# SCH_NRF_Rapid_Test_Board_2021-07-05.net
KiCad netlist of a schematic drawn in EasyEDA
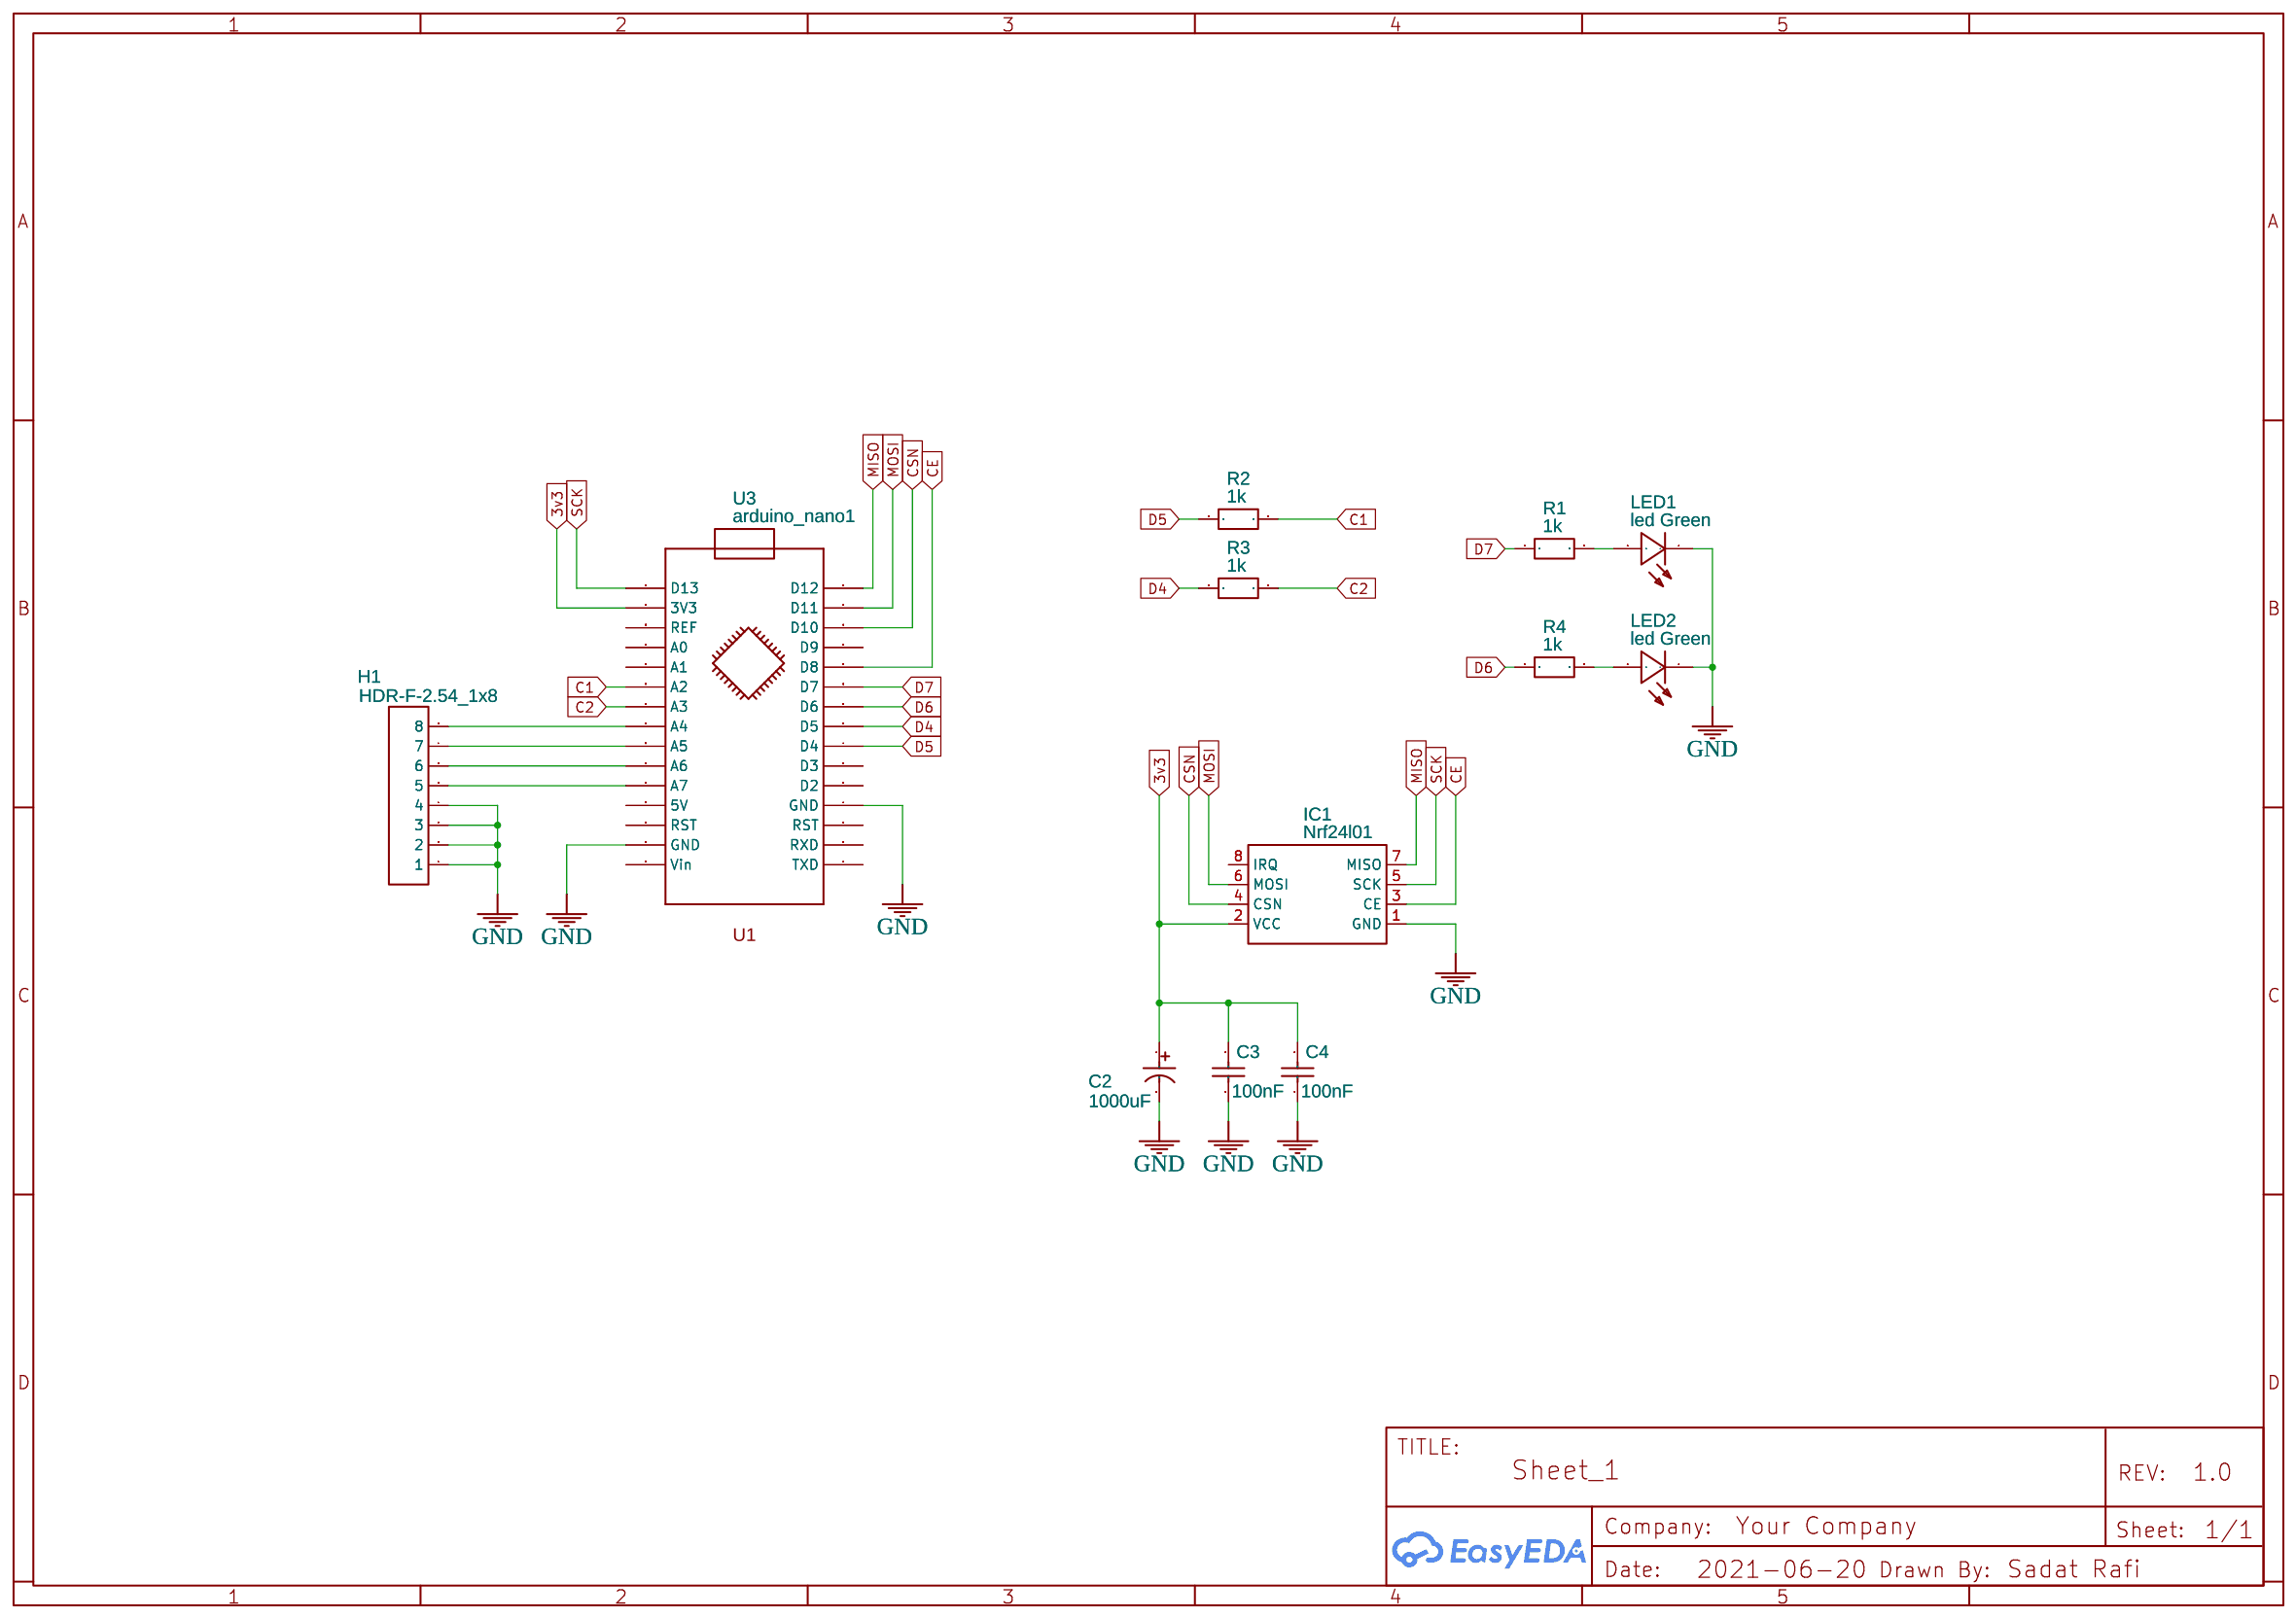
[diagram p0: schematic sheet]

(export (version "E")
  (design (tool "Eeschema 10.0.6"))
  (components
    (comp (ref "C2")
      (value "1000uF")
      (fields (field (name "BOM_Manufacturer Part") "1000uF 16V") (field (name "BOM_Supplier Part") "C43909"))
      (libsource (lib "") (part "1000uF 16V"))
    )
    (comp (ref "C3")
      (value "100nF")
      (fields
        (field (name "BOM_Manufacturer Part") "CL31B104KBCNNNC")
        (field (name "BOM_Supplier Part") "C24497")
      )
      (libsource (lib "") (part "CL31B104KBCNNNC"))
    )
    (comp (ref "C4")
      (value "100nF")
      (fields
        (field (name "BOM_Manufacturer Part") "CL31B104KBCNNNC")
        (field (name "BOM_Supplier Part") "C24497")
      )
      (libsource (lib "") (part "CL31B104KBCNNNC"))
    )
    (comp (ref "H1")
      (value "HDR-F-2.54_1x8")
      (fields (field (name "BOM_Supplier Part") "C225505"))
      (libsource (lib "") (part "HDR-F-2.54_1x8"))
    )
    (comp (ref "IC1")
      (value "Nrf24l01")
      (fields (field (name "BOM_Manufacturer Part") "NRF24L01") (field (name "BOM_Supplier Part") "01"))
      (libsource (lib "") (part "Nrf24l01"))
    )
    (comp (ref "LED1")
      (value "led Green")
      (fields (field (name "BOM_Supplier Part") "C14641"))
      (libsource (lib "") (part "led Green"))
    )
    (comp (ref "LED2")
      (value "led Green")
      (fields (field (name "BOM_Supplier Part") "C14641"))
      (libsource (lib "") (part "led Green"))
    )
    (comp (ref "R1") (value "1k") (libsource (lib "") (part "R_1206_EU")))
    (comp (ref "R2") (value "1k") (libsource (lib "") (part "R_1206_EU")))
    (comp (ref "R3") (value "1k") (libsource (lib "") (part "R_1206_EU")))
    (comp (ref "R4") (value "1k") (libsource (lib "") (part "R_1206_EU")))
    (comp (ref "U3") (value "arduino_nano1") (libsource (lib "") (part "arduino_nano1")))
  )
  (nets
    (net (code "1") (name "3v3") (class "Default")
      (node (ref "C2") (pin "1") (pinfunction "1_1") (pintype "input"))
      (node (ref "C3") (pin "2") (pinfunction "2_2") (pintype "input"))
      (node (ref "C4") (pin "2") (pinfunction "2_2") (pintype "input"))
      (node (ref "IC1") (pin "2") (pinfunction "VCC_2") (pintype "unspecified"))
      (node (ref "U3") (pin "17") (pinfunction "3V3_17") (pintype "unspecified"))
    )
    (net (code "2") (name "C1") (class "Default")
      (node (ref "R2") (pin "2") (pinfunction "2_2") (pintype "unspecified"))
      (node (ref "U3") (pin "21") (pinfunction "A2_21") (pintype "unspecified"))
    )
    (net (code "3") (name "C2") (class "Default")
      (node (ref "R3") (pin "2") (pinfunction "2_2") (pintype "unspecified"))
      (node (ref "U3") (pin "22") (pinfunction "A3_22") (pintype "unspecified"))
    )
    (net (code "4") (name "CE") (class "Default")
      (node (ref "IC1") (pin "3") (pinfunction "CE_3") (pintype "unspecified"))
      (node (ref "U3") (pin "11") (pinfunction "D8_11") (pintype "unspecified"))
    )
    (net (code "5") (name "CSN") (class "Default")
      (node (ref "IC1") (pin "4") (pinfunction "CSN_4") (pintype "unspecified"))
      (node (ref "U3") (pin "13") (pinfunction "D10_13") (pintype "unspecified"))
    )
    (net (code "6") (name "D4") (class "Default")
      (node (ref "R3") (pin "1") (pinfunction "1_1") (pintype "unspecified"))
      (node (ref "U3") (pin "8") (pinfunction "D5_8") (pintype "unspecified"))
    )
    (net (code "7") (name "D5") (class "Default")
      (node (ref "R2") (pin "1") (pinfunction "1_1") (pintype "unspecified"))
      (node (ref "U3") (pin "7") (pinfunction "D4_7") (pintype "unspecified"))
    )
    (net (code "8") (name "D6") (class "Default")
      (node (ref "R4") (pin "1") (pinfunction "1_1") (pintype "unspecified"))
      (node (ref "U3") (pin "9") (pinfunction "D6_9") (pintype "unspecified"))
    )
    (net (code "9") (name "D7") (class "Default")
      (node (ref "R1") (pin "1") (pinfunction "1_1") (pintype "unspecified"))
      (node (ref "U3") (pin "10") (pinfunction "D7_10") (pintype "unspecified"))
    )
    (net (code "10") (name "GND") (class "Default")
      (node (ref "C2") (pin "2") (pinfunction "2_2") (pintype "input"))
      (node (ref "C3") (pin "1") (pinfunction "1_1") (pintype "input"))
      (node (ref "C4") (pin "1") (pinfunction "1_1") (pintype "input"))
      (node (ref "H1") (pin "1") (pinfunction "1_1") (pintype "unspecified"))
      (node (ref "H1") (pin "2") (pinfunction "2_2") (pintype "unspecified"))
      (node (ref "H1") (pin "3") (pinfunction "3_3") (pintype "unspecified"))
      (node (ref "H1") (pin "4") (pinfunction "4_4") (pintype "unspecified"))
      (node (ref "IC1") (pin "1") (pinfunction "GND_1") (pintype "unspecified"))
      (node (ref "LED1") (pin "1") (pinfunction "-_1") (pintype "unspecified"))
      (node (ref "LED2") (pin "1") (pinfunction "-_1") (pintype "unspecified"))
      (node (ref "U3") (pin "29") (pinfunction "GND_29") (pintype "unspecified"))
      (node (ref "U3") (pin "4") (pinfunction "GND_4") (pintype "unspecified"))
    )
    (net (code "11") (name "MISO") (class "Default")
      (node (ref "IC1") (pin "7") (pinfunction "MISO_7") (pintype "unspecified"))
      (node (ref "U3") (pin "15") (pinfunction "D12_15") (pintype "unspecified"))
    )
    (net (code "12") (name "MOSI") (class "Default")
      (node (ref "IC1") (pin "6") (pinfunction "MOSI_6") (pintype "unspecified"))
      (node (ref "U3") (pin "14") (pinfunction "D11_14") (pintype "unspecified"))
    )
    (net (code "13") (name "Net-(LED1-+)") (class "Default")
      (node (ref "LED1") (pin "2") (pinfunction "+_2") (pintype "unspecified"))
      (node (ref "R1") (pin "2") (pinfunction "2_2") (pintype "unspecified"))
    )
    (net (code "14") (name "Net-(LED2-+)") (class "Default")
      (node (ref "LED2") (pin "2") (pinfunction "+_2") (pintype "unspecified"))
      (node (ref "R4") (pin "2") (pinfunction "2_2") (pintype "unspecified"))
    )
    (net (code "15") (name "Net-(U3-A4)") (class "Default")
      (node (ref "H1") (pin "8") (pinfunction "8_8") (pintype "unspecified"))
      (node (ref "U3") (pin "23") (pinfunction "A4_23") (pintype "unspecified"))
    )
    (net (code "16") (name "Net-(U3-A5)") (class "Default")
      (node (ref "H1") (pin "7") (pinfunction "7_7") (pintype "unspecified"))
      (node (ref "U3") (pin "24") (pinfunction "A5_24") (pintype "unspecified"))
    )
    (net (code "17") (name "Net-(U3-A6)") (class "Default")
      (node (ref "H1") (pin "6") (pinfunction "6_6") (pintype "unspecified"))
      (node (ref "U3") (pin "25") (pinfunction "A6_25") (pintype "unspecified"))
    )
    (net (code "18") (name "Net-(U3-A7)") (class "Default")
      (node (ref "H1") (pin "5") (pinfunction "5_5") (pintype "unspecified"))
      (node (ref "U3") (pin "26") (pinfunction "A7_26") (pintype "unspecified"))
    )
    (net (code "19") (name "SCK") (class "Default")
      (node (ref "IC1") (pin "5") (pinfunction "SCK_5") (pintype "unspecified"))
      (node (ref "U3") (pin "16") (pinfunction "D13_16") (pintype "unspecified"))
    )
    (net (code "20") (name "unconnected-(IC1-IRQ-Pad8)") (class "Default")
      (node (ref "IC1") (pin "8") (pinfunction "IRQ_8") (pintype "unspecified"))
    )
    (net (code "21") (name "unconnected-(U3-5V-Pad27)") (class "Default")
      (node (ref "U3") (pin "27") (pinfunction "5V_27") (pintype "unspecified"))
    )
    (net (code "22") (name "unconnected-(U3-A0-Pad19)") (class "Default")
      (node (ref "U3") (pin "19") (pinfunction "A0_19") (pintype "unspecified"))
    )
    (net (code "23") (name "unconnected-(U3-A1-Pad20)") (class "Default")
      (node (ref "U3") (pin "20") (pinfunction "A1_20") (pintype "unspecified"))
    )
    (net (code "24") (name "unconnected-(U3-D2-Pad5)") (class "Default")
      (node (ref "U3") (pin "5") (pinfunction "D2_5") (pintype "unspecified"))
    )
    (net (code "25") (name "unconnected-(U3-D3-Pad6)") (class "Default")
      (node (ref "U3") (pin "6") (pinfunction "D3_6") (pintype "unspecified"))
    )
    (net (code "26") (name "unconnected-(U3-D9-Pad12)") (class "Default")
      (node (ref "U3") (pin "12") (pinfunction "D9_12") (pintype "unspecified"))
    )
    (net (code "27") (name "unconnected-(U3-REF-Pad18)") (class "Default")
      (node (ref "U3") (pin "18") (pinfunction "REF_18") (pintype "unspecified"))
    )
    (net (code "28") (name "unconnected-(U3-RST-Pad3)") (class "Default")
      (node (ref "U3") (pin "3") (pinfunction "RST_3") (pintype "unspecified"))
    )
    (net (code "29") (name "unconnected-(U3-RST-Pad28)") (class "Default")
      (node (ref "U3") (pin "28") (pinfunction "RST_28") (pintype "unspecified"))
    )
    (net (code "30") (name "unconnected-(U3-RXD-Pad2)") (class "Default")
      (node (ref "U3") (pin "2") (pinfunction "RXD_2") (pintype "unspecified"))
    )
    (net (code "31") (name "unconnected-(U3-TXD-Pad1)") (class "Default")
      (node (ref "U3") (pin "1") (pinfunction "TXD_1") (pintype "unspecified"))
    )
    (net (code "32") (name "unconnected-(U3-Vin-Pad30)") (class "Default")
      (node (ref "U3") (pin "30") (pinfunction "Vin_30") (pintype "unspecified"))
    )
  )
)
